# IHM.net
KiCad netlist of a schematic drawn in EAGLE
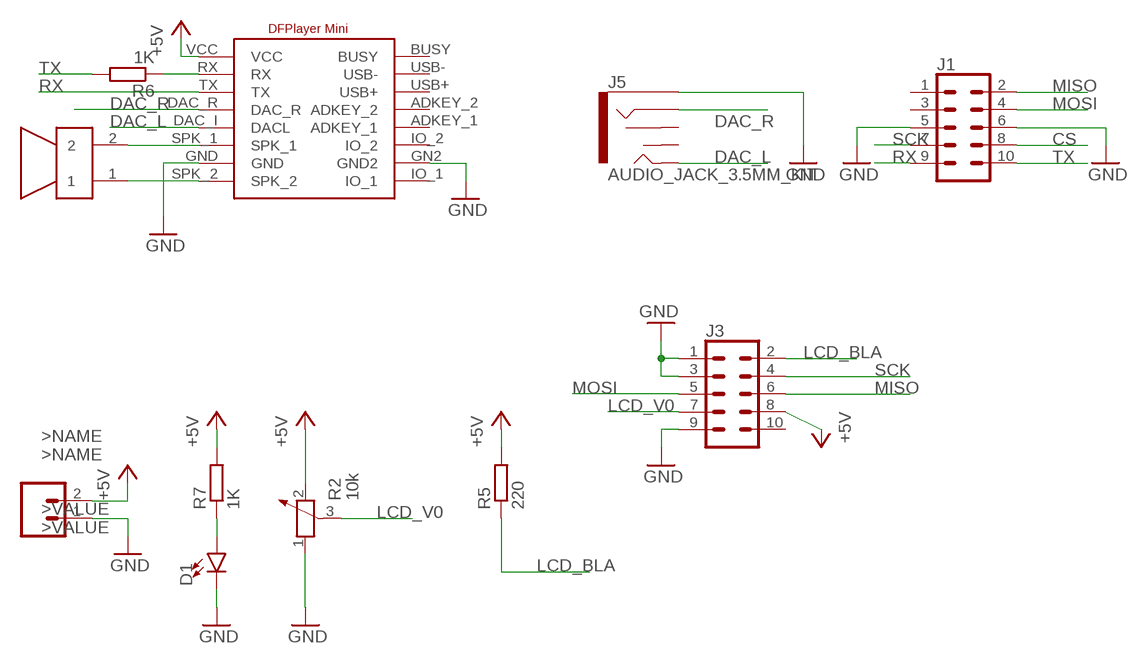
[diagram p0: schematic, sheet 1]

(export (version "E")
  (design (tool "Eeschema 10.0.6"))
  (components
    (comp (ref "D1")
      (value "LED3MM")
      (footprint "eagle-import:LED_3MM")
      (libsource (lib "eagle-import") (part "LED3MM"))
    )
    (comp (ref "J1")
      (value "CONN_05X2SHD")
      (footprint "eagle-import:2X5-SHROUDED")
      (libsource (lib "eagle-import") (part "CONN_05X2SHD"))
    )
    (comp (ref "J2")
      (value "CONN_02POLAR")
      (footprint "eagle-import:MOLEX-1X2")
      (libsource (lib "eagle-import") (part "CONN_02POLAR"))
    )
    (comp (ref "J3")
      (value "CONN_05X2SHD")
      (footprint "eagle-import:2X5-SHROUDED")
      (libsource (lib "eagle-import") (part "CONN_05X2SHD"))
    )
    (comp (ref "J5")
      (value "AUDIO_JACK_3.5MM_KIT")
      (footprint "eagle-import:AUDIO-JACK-KIT")
      (libsource (lib "eagle-import") (part "AUDIO_JACK_3.5MM_KIT"))
    )
    (comp (ref "R2")
      (value "10k")
      (footprint "eagle-import:PT-10")
      (libsource (lib "eagle-import") (part "POTENTIOMETER_PT-10"))
    )
    (comp (ref "R5")
      (value "220")
      (footprint "eagle-import:0207_10")
      (libsource (lib "eagle-import") (part "R-EU_0207/10"))
    )
    (comp (ref "R6")
      (value "1K")
      (footprint "eagle-import:0207_10")
      (libsource (lib "eagle-import") (part "R-EU_0207/10"))
    )
    (comp (ref "R7")
      (value "1K")
      (footprint "eagle-import:0207_10")
      (libsource (lib "eagle-import") (part "R-EU_0207/10"))
    )
    (comp (ref "U$1")
      (value "AST-01508MR-WT-R")
      (footprint "eagle-import:AST-01508MR-WT-R")
      (libsource (lib "eagle-import") (part "AST-01508MR-WT-R"))
    )
    (comp (ref "U$2")
      (value "DFPLAYER_MINI")
      (footprint "eagle-import:DFPLAYER_MINI")
      (libsource (lib "eagle-import") (part "DFPLAYER_MINI"))
    )
  )
  (nets
    (net (code "1") (name "+5V") (class "Default")
      (node (ref "J2") (pin "2") (pinfunction "2_2") (pintype "passive"))
      (node (ref "J3") (pin "8") (pinfunction "8_8") (pintype "passive"))
      (node (ref "R2") (pin "2") (pinfunction "2_2") (pintype "passive"))
      (node (ref "R5") (pin "2") (pinfunction "2_2") (pintype "passive"))
      (node (ref "R7") (pin "2") (pinfunction "2_2") (pintype "passive"))
      (node (ref "U$2") (pin "VCC") (pinfunction "VCC_VCC") (pintype "bidirectional"))
    )
    (net (code "2") (name "/CS") (class "Default")
      (node (ref "J1") (pin "8") (pinfunction "8_8") (pintype "passive"))
    )
    (net (code "3") (name "/DAC_L") (class "Default")
      (node (ref "J5") (pin "TIP") (pinfunction "TIP_TIP") (pintype "bidirectional"))
      (node (ref "U$2") (pin "DAC_I") (pinfunction "DACL_DAC_I") (pintype "bidirectional"))
    )
    (net (code "4") (name "/DAC_R") (class "Default")
      (node (ref "J5") (pin "RING") (pinfunction "RING_RING") (pintype "bidirectional"))
      (node (ref "U$2") (pin "DAC_R") (pinfunction "DAC_R_DAC_R") (pintype "bidirectional"))
    )
    (net (code "5") (name "/LCD_BLA") (class "Default")
      (node (ref "J3") (pin "2") (pinfunction "2_2") (pintype "passive"))
      (node (ref "R5") (pin "1") (pinfunction "1_1") (pintype "passive"))
    )
    (net (code "6") (name "/LCD_V0") (class "Default")
      (node (ref "J3") (pin "7") (pinfunction "7_7") (pintype "passive"))
      (node (ref "R2") (pin "3") (pinfunction "3_3") (pintype "passive"))
    )
    (net (code "7") (name "/MISO") (class "Default")
      (node (ref "J1") (pin "2") (pinfunction "2_2") (pintype "passive"))
      (node (ref "J3") (pin "6") (pinfunction "6_6") (pintype "passive"))
    )
    (net (code "8") (name "/MOSI") (class "Default")
      (node (ref "J1") (pin "4") (pinfunction "4_4") (pintype "passive"))
      (node (ref "J3") (pin "5") (pinfunction "5_5") (pintype "passive"))
    )
    (net (code "9") (name "/RX") (class "Default")
      (node (ref "J1") (pin "9") (pinfunction "9_9") (pintype "passive"))
      (node (ref "U$2") (pin "TX") (pinfunction "TX_TX") (pintype "bidirectional"))
    )
    (net (code "10") (name "/SCK") (class "Default")
      (node (ref "J1") (pin "7") (pinfunction "7_7") (pintype "passive"))
      (node (ref "J3") (pin "4") (pinfunction "4_4") (pintype "passive"))
    )
    (net (code "11") (name "/TX") (class "Default")
      (node (ref "J1") (pin "10") (pinfunction "10_10") (pintype "passive"))
      (node (ref "R6") (pin "2") (pinfunction "2_2") (pintype "passive"))
    )
    (net (code "12") (name "GND") (class "Default")
      (node (ref "D1") (pin "K") (pinfunction "C_K") (pintype "passive"))
      (node (ref "J1") (pin "5") (pinfunction "5_5") (pintype "passive"))
      (node (ref "J1") (pin "6") (pinfunction "6_6") (pintype "passive"))
      (node (ref "J2") (pin "1") (pinfunction "1_1") (pintype "passive"))
      (node (ref "J3") (pin "1") (pinfunction "1_1") (pintype "passive"))
      (node (ref "J3") (pin "3") (pinfunction "3_3") (pintype "passive"))
      (node (ref "J3") (pin "9") (pinfunction "9_9") (pintype "passive"))
      (node (ref "J5") (pin "SLEEVE") (pinfunction "SLEEVE_SLEEVE") (pintype "bidirectional"))
      (node (ref "R2") (pin "1") (pinfunction "1_1") (pintype "passive"))
      (node (ref "U$2") (pin "GN2") (pinfunction "GND2_GN2") (pintype "bidirectional"))
      (node (ref "U$2") (pin "GND") (pinfunction "GND_GND") (pintype "bidirectional"))
    )
    (net (code "13") (name "Net-(D1-PadA)") (class "Default")
      (node (ref "D1") (pin "A") (pinfunction "A_A") (pintype "passive"))
      (node (ref "R7") (pin "1") (pinfunction "1_1") (pintype "passive"))
    )
    (net (code "14") (name "Net-(R6-Pad1)") (class "Default")
      (node (ref "R6") (pin "1") (pinfunction "1_1") (pintype "passive"))
      (node (ref "U$2") (pin "RX") (pinfunction "RX_RX") (pintype "bidirectional"))
    )
    (net (code "15") (name "Net-(U$1-Pad1)") (class "Default")
      (node (ref "U$1") (pin "1") (pinfunction "1_1") (pintype "bidirectional"))
      (node (ref "U$2") (pin "SPK_2") (pinfunction "SPK_2_SPK_2") (pintype "bidirectional"))
    )
    (net (code "16") (name "Net-(U$1-Pad2)") (class "Default")
      (node (ref "U$1") (pin "2") (pinfunction "2_2") (pintype "bidirectional"))
      (node (ref "U$2") (pin "SPK_1") (pinfunction "SPK_1_SPK_1") (pintype "bidirectional"))
    )
    (net (code "17") (name "unconnected-(J1-Pad1)") (class "Default")
      (node (ref "J1") (pin "1") (pinfunction "1_1") (pintype "passive"))
    )
    (net (code "18") (name "unconnected-(J1-Pad3)") (class "Default")
      (node (ref "J1") (pin "3") (pinfunction "3_3") (pintype "passive"))
    )
    (net (code "19") (name "unconnected-(J3-Pad10)") (class "Default")
      (node (ref "J3") (pin "10") (pinfunction "10_10") (pintype "passive"))
    )
    (net (code "20") (name "unconnected-(J5-PadRSH)") (class "Default")
      (node (ref "J5") (pin "RSH") (pinfunction "RSH_RSH") (pintype "bidirectional"))
    )
    (net (code "21") (name "unconnected-(J5-PadTSH)") (class "Default")
      (node (ref "J5") (pin "TSH") (pinfunction "TSH_TSH") (pintype "bidirectional"))
    )
    (net (code "22") (name "unconnected-(U$2-PadADKEY_1)") (class "Default")
      (node (ref "U$2") (pin "ADKEY_1") (pinfunction "ADKEY_1_ADKEY_1") (pintype "bidirectional"))
    )
    (net (code "23") (name "unconnected-(U$2-PadADKEY_2)") (class "Default")
      (node (ref "U$2") (pin "ADKEY_2") (pinfunction "ADKEY_2_ADKEY_2") (pintype "bidirectional"))
    )
    (net (code "24") (name "unconnected-(U$2-PadBUSY)") (class "Default")
      (node (ref "U$2") (pin "BUSY") (pinfunction "BUSY_BUSY") (pintype "bidirectional"))
    )
    (net (code "25") (name "unconnected-(U$2-PadIO_1)") (class "Default")
      (node (ref "U$2") (pin "IO_1") (pinfunction "IO_1_IO_1") (pintype "bidirectional"))
    )
    (net (code "26") (name "unconnected-(U$2-PadIO_2)") (class "Default")
      (node (ref "U$2") (pin "IO_2") (pinfunction "IO_2_IO_2") (pintype "bidirectional"))
    )
    (net (code "27") (name "unconnected-(U$2-PadUSB+)") (class "Default")
      (node (ref "U$2") (pin "USB+") (pinfunction "USB+_USB+") (pintype "bidirectional"))
    )
    (net (code "28") (name "unconnected-(U$2-PadUSB-)") (class "Default")
      (node (ref "U$2") (pin "USB-") (pinfunction "USB-_USB-") (pintype "bidirectional"))
    )
  )
)
